# Power_3V3.net
KiCad netlist of a schematic drawn in Altium Designer
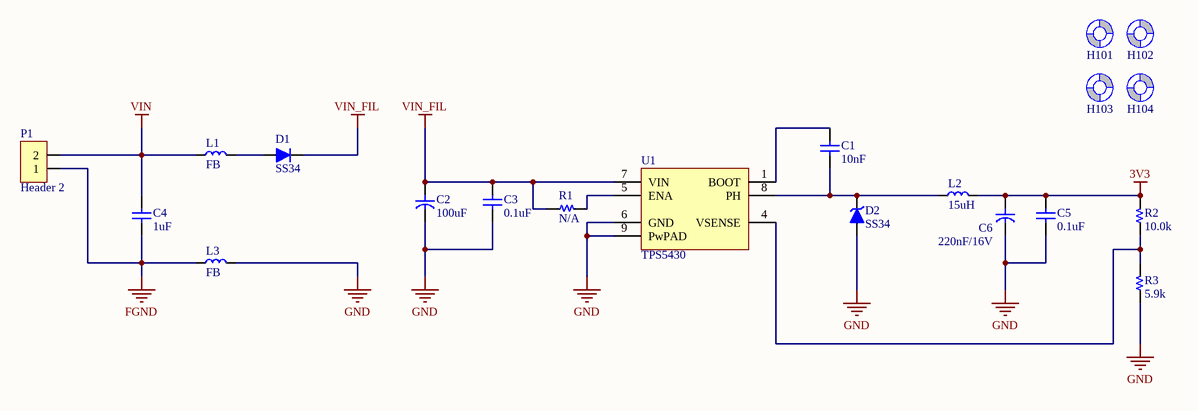
[diagram p0: Power_3V3.SchDoc]

(export (version "E")
  (design (tool "Eeschema 10.0.6"))
  (components
    (comp (ref "C1")
      (value "10nF")
      (footprint "C 0805")
      (description "Capacitor non-pol")
      (libsource (lib "chipfc_libs") (part "Capacitor NP"))
    )
    (comp (ref "C2")
      (value "100uF")
      (footprint "C SMD TAN 1206 (A)")
      (description "Capacitor pol")
      (libsource (lib "chipfc_libs") (part "Capacitor"))
    )
    (comp (ref "C3")
      (value "0.1uF")
      (footprint "C 0805")
      (description "Capacitor non-pol")
      (libsource (lib "chipfc_libs") (part "Capacitor NP"))
    )
    (comp (ref "C4")
      (value "1uF")
      (footprint "C 0805")
      (description "Capacitor non-pol")
      (libsource (lib "chipfc_libs") (part "Capacitor NP"))
    )
    (comp (ref "C5")
      (value "0.1uF")
      (footprint "C 0805")
      (description "Capacitor non-pol")
      (libsource (lib "chipfc_libs") (part "Capacitor NP"))
    )
    (comp (ref "C6")
      (value "220nF/16V")
      (footprint "C SMD TAN 1206 (A)")
      (description "Capacitor pol")
      (libsource (lib "chipfc_libs") (part "Capacitor"))
    )
    (comp (ref "D1")
      (value "SS34")
      (footprint "DO-35 (SOD27 )")
      (description "Default Diode")
      (libsource (lib "chipfc_libs") (part "Diode"))
    )
    (comp (ref "D2")
      (value "SS34")
      (footprint "DO-214AC (SMA)")
      (description "Zener Diode")
      (libsource (lib "chipfc_libs") (part "Diode Zener"))
    )
    (comp (ref "H101")
      (value "Screw Hole")
      (footprint "SCREW/3.2/7.0/M")
      (libsource (lib "chipfc_libs") (part "Screw Hole"))
    )
    (comp (ref "H102")
      (value "Screw Hole")
      (footprint "SCREW/3.2/7.0/M")
      (libsource (lib "chipfc_libs") (part "Screw Hole"))
    )
    (comp (ref "H103")
      (value "Screw Hole")
      (footprint "SCREW/3.2/7.0/M")
      (libsource (lib "chipfc_libs") (part "Screw Hole"))
    )
    (comp (ref "H104")
      (value "Screw Hole")
      (footprint "SCREW/3.2/7.0/M")
      (libsource (lib "chipfc_libs") (part "Screw Hole"))
    )
    (comp (ref "L1")
      (value "FB")
      (footprint "Inductor SMD 0805 (2012)")
      (description "Inductor")
      (libsource (lib "chipfc_libs") (part "Inductor"))
    )
    (comp (ref "L2")
      (value "15uH")
      (footprint "Inductor SMD 0805 (2012)")
      (description "Inductor")
      (libsource (lib "chipfc_libs") (part "Inductor"))
    )
    (comp (ref "L3")
      (value "FB")
      (footprint "Inductor SMD 0805 (2012)")
      (description "Inductor")
      (libsource (lib "chipfc_libs") (part "Inductor"))
    )
    (comp (ref "P1")
      (value "Header 2")
      (footprint "HDR/Header/2/BOX/RED")
      (description "Header, 2-Pin")
      (libsource (lib "connectors") (part "Header 2"))
    )
    (comp (ref "R1")
      (value "N/A")
      (footprint "R 0805")
      (description "Resistor")
      (libsource (lib "chipfc_libs") (part "Resistor"))
    )
    (comp (ref "R2")
      (value "10.0k")
      (footprint "R 0805")
      (description "Resistor")
      (libsource (lib "chipfc_libs") (part "Resistor"))
    )
    (comp (ref "R3")
      (value "5.9k")
      (footprint "R 0805")
      (description "Resistor")
      (libsource (lib "chipfc_libs") (part "Resistor"))
    )
    (comp (ref "U1")
      (value "TPS5430")
      (footprint "SOIC-8 EP")
      (description "3/5A, Wide input range, Step-down SWIFT DC-DC Converter")
      (libsource (lib "chipfc_libs") (part "TPS54xx"))
    )
  )
  (nets
    (net (code "1") (name "3V3") (class "Default")
      (node (ref "C5") (pin "1") (pinfunction "1_1") (pintype "passive"))
      (node (ref "C6") (pin "1") (pinfunction "1_1") (pintype "passive"))
      (node (ref "L2") (pin "2") (pinfunction "2_2") (pintype "passive"))
      (node (ref "R2") (pin "2") (pinfunction "2_2") (pintype "passive"))
    )
    (net (code "2") (name "FGND") (class "Default")
      (node (ref "C4") (pin "2") (pinfunction "2_2") (pintype "passive"))
      (node (ref "L3") (pin "1") (pinfunction "1_1") (pintype "passive"))
      (node (ref "P1") (pin "1") (pinfunction "1_1") (pintype "passive"))
    )
    (net (code "3") (name "GND") (class "Default")
      (node (ref "C2") (pin "2") (pinfunction "2_2") (pintype "passive"))
      (node (ref "C3") (pin "2") (pinfunction "2_2") (pintype "passive"))
      (node (ref "C5") (pin "2") (pinfunction "2_2") (pintype "passive"))
      (node (ref "C6") (pin "2") (pinfunction "2_2") (pintype "passive"))
      (node (ref "D2") (pin "1") (pinfunction "A_1") (pintype "passive"))
      (node (ref "L3") (pin "2") (pinfunction "2_2") (pintype "passive"))
      (node (ref "R3") (pin "1") (pinfunction "1_1") (pintype "passive"))
      (node (ref "U1") (pin "6") (pinfunction "GND_6") (pintype "passive"))
      (node (ref "U1") (pin "9") (pinfunction "PwPAD_9") (pintype "passive"))
    )
    (net (code "4") (name "Net-(D1-A)") (class "Default")
      (node (ref "D1") (pin "1") (pinfunction "A_1") (pintype "passive"))
      (node (ref "L1") (pin "2") (pinfunction "2_2") (pintype "passive"))
    )
    (net (code "5") (name "Net-(D2-K)") (class "Default")
      (node (ref "C1") (pin "2") (pinfunction "2_2") (pintype "passive"))
      (node (ref "D2") (pin "2") (pinfunction "K_2") (pintype "passive"))
      (node (ref "L2") (pin "1") (pinfunction "1_1") (pintype "passive"))
      (node (ref "U1") (pin "8") (pinfunction "PH_8") (pintype "passive"))
    )
    (net (code "6") (name "Net-(U1-BOOT)") (class "Default")
      (node (ref "C1") (pin "1") (pinfunction "1_1") (pintype "passive"))
      (node (ref "U1") (pin "1") (pinfunction "BOOT_1") (pintype "passive"))
    )
    (net (code "7") (name "Net-(U1-ENA)") (class "Default")
      (node (ref "R1") (pin "2") (pinfunction "2_2") (pintype "passive"))
      (node (ref "U1") (pin "5") (pinfunction "ENA_5") (pintype "passive"))
    )
    (net (code "8") (name "Net-(U1-VSENSE)") (class "Default")
      (node (ref "R2") (pin "1") (pinfunction "1_1") (pintype "passive"))
      (node (ref "R3") (pin "2") (pinfunction "2_2") (pintype "passive"))
      (node (ref "U1") (pin "4") (pinfunction "VSENSE_4") (pintype "passive"))
    )
    (net (code "9") (name "VIN") (class "Default")
      (node (ref "C4") (pin "1") (pinfunction "1_1") (pintype "passive"))
      (node (ref "L1") (pin "1") (pinfunction "1_1") (pintype "passive"))
      (node (ref "P1") (pin "2") (pinfunction "2_2") (pintype "passive"))
    )
    (net (code "10") (name "VIN_FIL") (class "Default")
      (node (ref "C2") (pin "1") (pinfunction "1_1") (pintype "passive"))
      (node (ref "C3") (pin "1") (pinfunction "1_1") (pintype "passive"))
      (node (ref "D1") (pin "2") (pinfunction "K_2") (pintype "passive"))
      (node (ref "R1") (pin "1") (pinfunction "1_1") (pintype "passive"))
      (node (ref "U1") (pin "7") (pinfunction "VIN_7") (pintype "passive"))
    )
    (net (code "11") (name "unconnected-(H101-Screw-Pad1)") (class "Default")
      (node (ref "H101") (pin "1") (pinfunction "Screw_1") (pintype "passive"))
    )
    (net (code "12") (name "unconnected-(H102-Screw-Pad1)") (class "Default")
      (node (ref "H102") (pin "1") (pinfunction "Screw_1") (pintype "passive"))
    )
    (net (code "13") (name "unconnected-(H103-Screw-Pad1)") (class "Default")
      (node (ref "H103") (pin "1") (pinfunction "Screw_1") (pintype "passive"))
    )
    (net (code "14") (name "unconnected-(H104-Screw-Pad1)") (class "Default")
      (node (ref "H104") (pin "1") (pinfunction "Screw_1") (pintype "passive"))
    )
  )
)
